# MCP23017_O8_v1_01.net
KiCad netlist of a schematic drawn in EAGLE
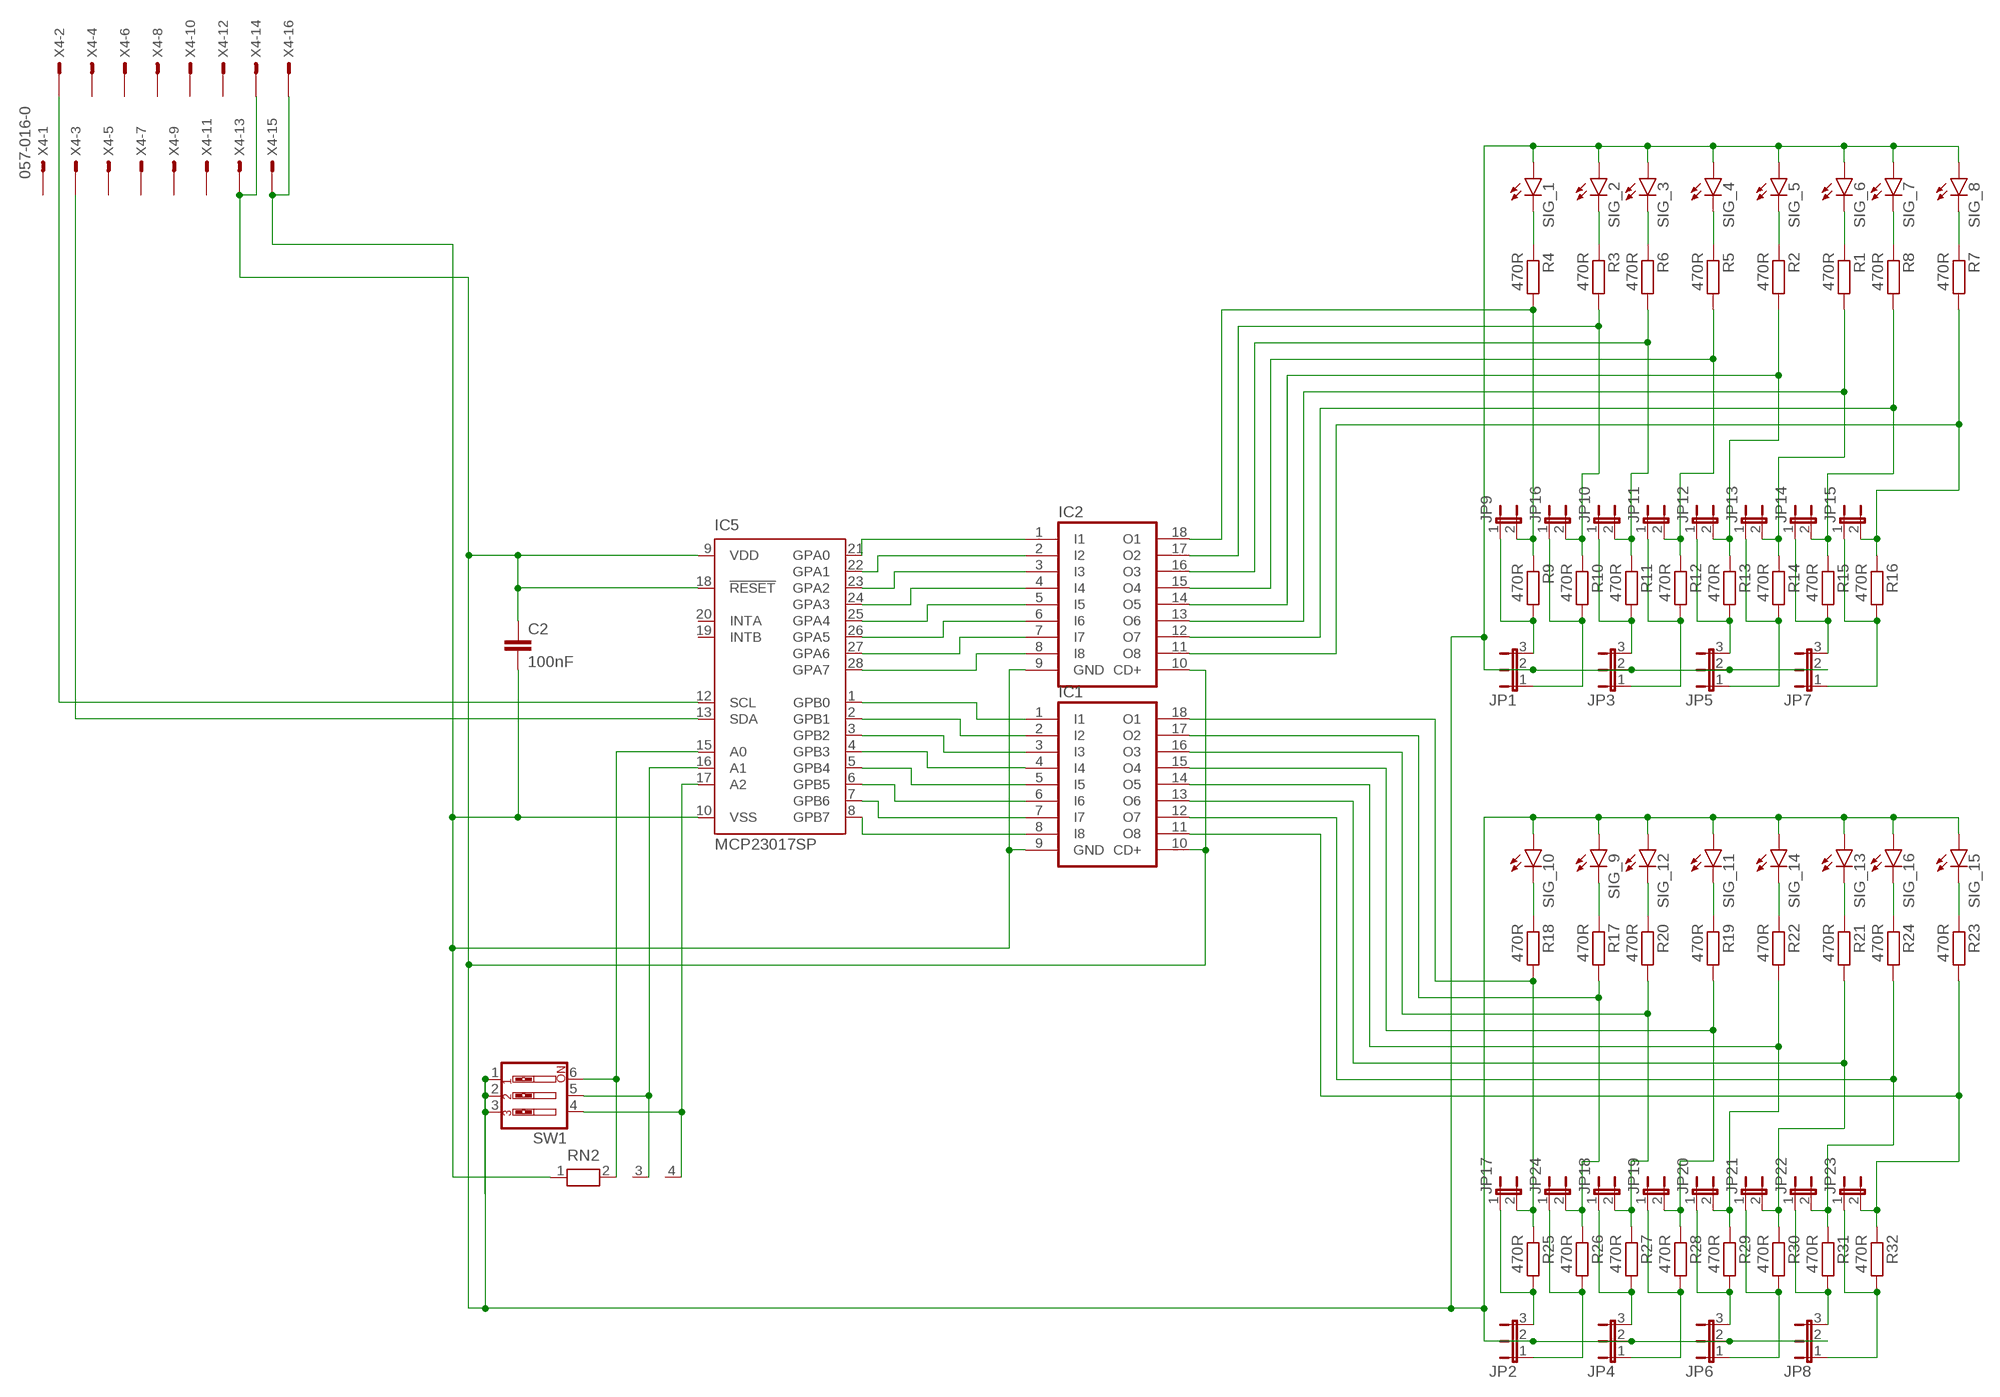
[diagram p0: schematic, sheet 1]

(export (version "E")
  (design (tool "Eeschema 10.0.6"))
  (components
    (comp (ref "C2")
      (value "100nF")
      (footprint "eagle-import:C025-024X044")
      (libsource (lib "eagle-import") (part "C-EU025-024X044"))
    )
    (comp (ref "IC1")
      (value "ULN2803A")
      (footprint "eagle-import:DIL18")
      (libsource (lib "eagle-import") (part "ULN2803A"))
    )
    (comp (ref "IC2")
      (value "ULN2803A")
      (footprint "eagle-import:DIL18")
      (libsource (lib "eagle-import") (part "ULN2803A"))
    )
    (comp (ref "IC5")
      (value "MCP23017SP")
      (footprint "eagle-import:DIL28-3")
      (libsource (lib "eagle-import") (part "MCP23017SP"))
    )
    (comp (ref "JP1")
      (value "JP2E")
      (footprint "eagle-import:JP2")
      (libsource (lib "eagle-import") (part "JP2E"))
    )
    (comp (ref "JP2")
      (value "JP2E")
      (footprint "eagle-import:JP2")
      (libsource (lib "eagle-import") (part "JP2E"))
    )
    (comp (ref "JP3")
      (value "JP2E")
      (footprint "eagle-import:JP2")
      (libsource (lib "eagle-import") (part "JP2E"))
    )
    (comp (ref "JP4")
      (value "JP2E")
      (footprint "eagle-import:JP2")
      (libsource (lib "eagle-import") (part "JP2E"))
    )
    (comp (ref "JP5")
      (value "JP2E")
      (footprint "eagle-import:JP2")
      (libsource (lib "eagle-import") (part "JP2E"))
    )
    (comp (ref "JP6")
      (value "JP2E")
      (footprint "eagle-import:JP2")
      (libsource (lib "eagle-import") (part "JP2E"))
    )
    (comp (ref "JP7")
      (value "JP2E")
      (footprint "eagle-import:JP2")
      (libsource (lib "eagle-import") (part "JP2E"))
    )
    (comp (ref "JP8")
      (value "JP2E")
      (footprint "eagle-import:JP2")
      (libsource (lib "eagle-import") (part "JP2E"))
    )
    (comp (ref "JP9")
      (value "JP1E")
      (footprint "eagle-import:JP1")
      (libsource (lib "eagle-import") (part "JP1E"))
    )
    (comp (ref "JP10")
      (value "JP1E")
      (footprint "eagle-import:JP1")
      (libsource (lib "eagle-import") (part "JP1E"))
    )
    (comp (ref "JP11")
      (value "JP1E")
      (footprint "eagle-import:JP1")
      (libsource (lib "eagle-import") (part "JP1E"))
    )
    (comp (ref "JP12")
      (value "JP1E")
      (footprint "eagle-import:JP1")
      (libsource (lib "eagle-import") (part "JP1E"))
    )
    (comp (ref "JP13")
      (value "JP1E")
      (footprint "eagle-import:JP1")
      (libsource (lib "eagle-import") (part "JP1E"))
    )
    (comp (ref "JP14")
      (value "JP1E")
      (footprint "eagle-import:JP1")
      (libsource (lib "eagle-import") (part "JP1E"))
    )
    (comp (ref "JP15")
      (value "JP1E")
      (footprint "eagle-import:JP1")
      (libsource (lib "eagle-import") (part "JP1E"))
    )
    (comp (ref "JP16")
      (value "JP1E")
      (footprint "eagle-import:JP1")
      (libsource (lib "eagle-import") (part "JP1E"))
    )
    (comp (ref "JP17")
      (value "JP1E")
      (footprint "eagle-import:JP1")
      (libsource (lib "eagle-import") (part "JP1E"))
    )
    (comp (ref "JP18")
      (value "JP1E")
      (footprint "eagle-import:JP1")
      (libsource (lib "eagle-import") (part "JP1E"))
    )
    (comp (ref "JP19")
      (value "JP1E")
      (footprint "eagle-import:JP1")
      (libsource (lib "eagle-import") (part "JP1E"))
    )
    (comp (ref "JP20")
      (value "JP1E")
      (footprint "eagle-import:JP1")
      (libsource (lib "eagle-import") (part "JP1E"))
    )
    (comp (ref "JP21")
      (value "JP1E")
      (footprint "eagle-import:JP1")
      (libsource (lib "eagle-import") (part "JP1E"))
    )
    (comp (ref "JP22")
      (value "JP1E")
      (footprint "eagle-import:JP1")
      (libsource (lib "eagle-import") (part "JP1E"))
    )
    (comp (ref "JP23")
      (value "JP1E")
      (footprint "eagle-import:JP1")
      (libsource (lib "eagle-import") (part "JP1E"))
    )
    (comp (ref "JP24")
      (value "JP1E")
      (footprint "eagle-import:JP1")
      (libsource (lib "eagle-import") (part "JP1E"))
    )
    (comp (ref "R1")
      (value "470R")
      (footprint "eagle-import:0309_10")
      (libsource (lib "eagle-import") (part "R-EU_0309/10"))
    )
    (comp (ref "R2")
      (value "470R")
      (footprint "eagle-import:0309_10")
      (libsource (lib "eagle-import") (part "R-EU_0309/10"))
    )
    (comp (ref "R3")
      (value "470R")
      (footprint "eagle-import:0309_10")
      (libsource (lib "eagle-import") (part "R-EU_0309/10"))
    )
    (comp (ref "R4")
      (value "470R")
      (footprint "eagle-import:0309_10")
      (libsource (lib "eagle-import") (part "R-EU_0309/10"))
    )
    (comp (ref "R5")
      (value "470R")
      (footprint "eagle-import:0309_10")
      (libsource (lib "eagle-import") (part "R-EU_0309/10"))
    )
    (comp (ref "R6")
      (value "470R")
      (footprint "eagle-import:0309_10")
      (libsource (lib "eagle-import") (part "R-EU_0309/10"))
    )
    (comp (ref "R7")
      (value "470R")
      (footprint "eagle-import:0309_10")
      (libsource (lib "eagle-import") (part "R-EU_0309/10"))
    )
    (comp (ref "R8")
      (value "470R")
      (footprint "eagle-import:0309_10")
      (libsource (lib "eagle-import") (part "R-EU_0309/10"))
    )
    (comp (ref "R9")
      (value "470R")
      (footprint "eagle-import:0309_10")
      (libsource (lib "eagle-import") (part "R-EU_0309/10"))
    )
    (comp (ref "R10")
      (value "470R")
      (footprint "eagle-import:0309_10")
      (libsource (lib "eagle-import") (part "R-EU_0309/10"))
    )
    (comp (ref "R11")
      (value "470R")
      (footprint "eagle-import:0309_10")
      (libsource (lib "eagle-import") (part "R-EU_0309/10"))
    )
    (comp (ref "R12")
      (value "470R")
      (footprint "eagle-import:0309_10")
      (libsource (lib "eagle-import") (part "R-EU_0309/10"))
    )
    (comp (ref "R13")
      (value "470R")
      (footprint "eagle-import:0309_10")
      (libsource (lib "eagle-import") (part "R-EU_0309/10"))
    )
    (comp (ref "R14")
      (value "470R")
      (footprint "eagle-import:0309_10")
      (libsource (lib "eagle-import") (part "R-EU_0309/10"))
    )
    (comp (ref "R15")
      (value "470R")
      (footprint "eagle-import:0309_10")
      (libsource (lib "eagle-import") (part "R-EU_0309/10"))
    )
    (comp (ref "R16")
      (value "470R")
      (footprint "eagle-import:0309_10")
      (libsource (lib "eagle-import") (part "R-EU_0309/10"))
    )
    (comp (ref "R17")
      (value "470R")
      (footprint "eagle-import:0309_10")
      (libsource (lib "eagle-import") (part "R-EU_0309/10"))
    )
    (comp (ref "R18")
      (value "470R")
      (footprint "eagle-import:0309_10")
      (libsource (lib "eagle-import") (part "R-EU_0309/10"))
    )
    (comp (ref "R19")
      (value "470R")
      (footprint "eagle-import:0309_10")
      (libsource (lib "eagle-import") (part "R-EU_0309/10"))
    )
    (comp (ref "R20")
      (value "470R")
      (footprint "eagle-import:0309_10")
      (libsource (lib "eagle-import") (part "R-EU_0309/10"))
    )
    (comp (ref "R21")
      (value "470R")
      (footprint "eagle-import:0309_10")
      (libsource (lib "eagle-import") (part "R-EU_0309/10"))
    )
    (comp (ref "R22")
      (value "470R")
      (footprint "eagle-import:0309_10")
      (libsource (lib "eagle-import") (part "R-EU_0309/10"))
    )
    (comp (ref "R23")
      (value "470R")
      (footprint "eagle-import:0309_10")
      (libsource (lib "eagle-import") (part "R-EU_0309/10"))
    )
    (comp (ref "R24")
      (value "470R")
      (footprint "eagle-import:0309_10")
      (libsource (lib "eagle-import") (part "R-EU_0309/10"))
    )
    (comp (ref "R25")
      (value "470R")
      (footprint "eagle-import:0309_10")
      (libsource (lib "eagle-import") (part "R-EU_0309/10"))
    )
    (comp (ref "R26")
      (value "470R")
      (footprint "eagle-import:0309_10")
      (libsource (lib "eagle-import") (part "R-EU_0309/10"))
    )
    (comp (ref "R27")
      (value "470R")
      (footprint "eagle-import:0309_10")
      (libsource (lib "eagle-import") (part "R-EU_0309/10"))
    )
    (comp (ref "R28")
      (value "470R")
      (footprint "eagle-import:0309_10")
      (libsource (lib "eagle-import") (part "R-EU_0309/10"))
    )
    (comp (ref "R29")
      (value "470R")
      (footprint "eagle-import:0309_10")
      (libsource (lib "eagle-import") (part "R-EU_0309/10"))
    )
    (comp (ref "R30")
      (value "470R")
      (footprint "eagle-import:0309_10")
      (libsource (lib "eagle-import") (part "R-EU_0309/10"))
    )
    (comp (ref "R31")
      (value "470R")
      (footprint "eagle-import:0309_10")
      (libsource (lib "eagle-import") (part "R-EU_0309/10"))
    )
    (comp (ref "R32")
      (value "470R")
      (footprint "eagle-import:0309_10")
      (libsource (lib "eagle-import") (part "R-EU_0309/10"))
    )
    (comp (ref "RN2")
      (value "RN03")
      (footprint "eagle-import:RN-3")
      (libsource (lib "eagle-import") (part "RN03"))
    )
    (comp (ref "SIG_1")
      (value "LED3MM")
      (footprint "eagle-import:LED3MM")
      (libsource (lib "eagle-import") (part "LED3MM"))
    )
    (comp (ref "SIG_2")
      (value "LED3MM")
      (footprint "eagle-import:LED3MM")
      (libsource (lib "eagle-import") (part "LED3MM"))
    )
    (comp (ref "SIG_3")
      (value "LED3MM")
      (footprint "eagle-import:LED3MM")
      (libsource (lib "eagle-import") (part "LED3MM"))
    )
    (comp (ref "SIG_4")
      (value "LED3MM")
      (footprint "eagle-import:LED3MM")
      (libsource (lib "eagle-import") (part "LED3MM"))
    )
    (comp (ref "SIG_5")
      (value "LED3MM")
      (footprint "eagle-import:LED3MM")
      (libsource (lib "eagle-import") (part "LED3MM"))
    )
    (comp (ref "SIG_6")
      (value "LED3MM")
      (footprint "eagle-import:LED3MM")
      (libsource (lib "eagle-import") (part "LED3MM"))
    )
    (comp (ref "SIG_7")
      (value "LED3MM")
      (footprint "eagle-import:LED3MM")
      (libsource (lib "eagle-import") (part "LED3MM"))
    )
    (comp (ref "SIG_8")
      (value "LED3MM")
      (footprint "eagle-import:LED3MM")
      (libsource (lib "eagle-import") (part "LED3MM"))
    )
    (comp (ref "SIG_9")
      (value "LED3MM")
      (footprint "eagle-import:LED3MM")
      (libsource (lib "eagle-import") (part "LED3MM"))
    )
    (comp (ref "SIG_10")
      (value "LED3MM")
      (footprint "eagle-import:LED3MM")
      (libsource (lib "eagle-import") (part "LED3MM"))
    )
    (comp (ref "SIG_11")
      (value "LED3MM")
      (footprint "eagle-import:LED3MM")
      (libsource (lib "eagle-import") (part "LED3MM"))
    )
    (comp (ref "SIG_12")
      (value "LED3MM")
      (footprint "eagle-import:LED3MM")
      (libsource (lib "eagle-import") (part "LED3MM"))
    )
    (comp (ref "SIG_13")
      (value "LED3MM")
      (footprint "eagle-import:LED3MM")
      (libsource (lib "eagle-import") (part "LED3MM"))
    )
    (comp (ref "SIG_14")
      (value "LED3MM")
      (footprint "eagle-import:LED3MM")
      (libsource (lib "eagle-import") (part "LED3MM"))
    )
    (comp (ref "SIG_15")
      (value "LED3MM")
      (footprint "eagle-import:LED3MM")
      (libsource (lib "eagle-import") (part "LED3MM"))
    )
    (comp (ref "SIG_16")
      (value "LED3MM")
      (footprint "eagle-import:LED3MM")
      (libsource (lib "eagle-import") (part "LED3MM"))
    )
    (comp (ref "SW1")
      (value "SW_DIP-3")
      (footprint "eagle-import:EDG-03")
      (libsource (lib "eagle-import") (part "SW_DIP-3"))
    )
    (comp (ref "X4")
      (value "057-016-0")
      (footprint "eagle-import:057-016-0")
      (libsource (lib "eagle-import") (part "057-016-0"))
    )
  )
  (nets
    (net (code "1") (name "Net-(IC1-CD+)") (class "Default")
      (node (ref "C2") (pin "1") (pinfunction "1_1") (pintype "passive"))
      (node (ref "IC1") (pin "10") (pinfunction "CD+_10") (pintype "passive"))
      (node (ref "IC2") (pin "10") (pinfunction "CD+_10") (pintype "passive"))
      (node (ref "IC5") (pin "18") (pinfunction "~{RESET}_18") (pintype "input"))
      (node (ref "IC5") (pin "9") (pinfunction "VDD_9") (pintype "power_in"))
      (node (ref "JP1") (pin "2") (pinfunction "2_2") (pintype "passive"))
      (node (ref "JP2") (pin "2") (pinfunction "2_2") (pintype "passive"))
      (node (ref "JP3") (pin "2") (pinfunction "2_2") (pintype "passive"))
      (node (ref "JP4") (pin "2") (pinfunction "2_2") (pintype "passive"))
      (node (ref "JP5") (pin "2") (pinfunction "2_2") (pintype "passive"))
      (node (ref "JP6") (pin "2") (pinfunction "2_2") (pintype "passive"))
      (node (ref "JP7") (pin "2") (pinfunction "2_2") (pintype "passive"))
      (node (ref "JP8") (pin "2") (pinfunction "2_2") (pintype "passive"))
      (node (ref "SIG_1") (pin "A") (pinfunction "A_A") (pintype "passive"))
      (node (ref "SIG_10") (pin "A") (pinfunction "A_A") (pintype "passive"))
      (node (ref "SIG_11") (pin "A") (pinfunction "A_A") (pintype "passive"))
      (node (ref "SIG_12") (pin "A") (pinfunction "A_A") (pintype "passive"))
      (node (ref "SIG_13") (pin "A") (pinfunction "A_A") (pintype "passive"))
      (node (ref "SIG_14") (pin "A") (pinfunction "A_A") (pintype "passive"))
      (node (ref "SIG_15") (pin "A") (pinfunction "A_A") (pintype "passive"))
      (node (ref "SIG_16") (pin "A") (pinfunction "A_A") (pintype "passive"))
      (node (ref "SIG_2") (pin "A") (pinfunction "A_A") (pintype "passive"))
      (node (ref "SIG_3") (pin "A") (pinfunction "A_A") (pintype "passive"))
      (node (ref "SIG_4") (pin "A") (pinfunction "A_A") (pintype "passive"))
      (node (ref "SIG_5") (pin "A") (pinfunction "A_A") (pintype "passive"))
      (node (ref "SIG_6") (pin "A") (pinfunction "A_A") (pintype "passive"))
      (node (ref "SIG_7") (pin "A") (pinfunction "A_A") (pintype "passive"))
      (node (ref "SIG_8") (pin "A") (pinfunction "A_A") (pintype "passive"))
      (node (ref "SIG_9") (pin "A") (pinfunction "A_A") (pintype "passive"))
      (node (ref "SW1") (pin "1") (pinfunction "1_1") (pintype "passive"))
      (node (ref "SW1") (pin "2") (pinfunction "2_2") (pintype "passive"))
      (node (ref "SW1") (pin "3") (pinfunction "3_3") (pintype "passive"))
      (node (ref "X4") (pin "13") (pinfunction "S_13") (pintype "passive"))
      (node (ref "X4") (pin "14") (pinfunction "S_14") (pintype "passive"))
    )
    (net (code "2") (name "Net-(IC1-GND)") (class "Default")
      (node (ref "C2") (pin "2") (pinfunction "2_2") (pintype "passive"))
      (node (ref "IC1") (pin "9") (pinfunction "GND_9") (pintype "power_in"))
      (node (ref "IC2") (pin "9") (pinfunction "GND_9") (pintype "power_in"))
      (node (ref "IC5") (pin "10") (pinfunction "VSS_10") (pintype "power_in"))
      (node (ref "RN2") (pin "1") (pinfunction "1_1") (pintype "passive"))
      (node (ref "X4") (pin "15") (pinfunction "S_15") (pintype "passive"))
      (node (ref "X4") (pin "16") (pinfunction "S_16") (pintype "passive"))
    )
    (net (code "3") (name "Net-(IC1-I1)") (class "Default")
      (node (ref "IC1") (pin "1") (pinfunction "I1_1") (pintype "input"))
      (node (ref "IC5") (pin "1") (pinfunction "GPB0_1") (pintype "bidirectional"))
    )
    (net (code "4") (name "Net-(IC1-I2)") (class "Default")
      (node (ref "IC1") (pin "2") (pinfunction "I2_2") (pintype "input"))
      (node (ref "IC5") (pin "2") (pinfunction "GPB1_2") (pintype "bidirectional"))
    )
    (net (code "5") (name "Net-(IC1-I3)") (class "Default")
      (node (ref "IC1") (pin "3") (pinfunction "I3_3") (pintype "input"))
      (node (ref "IC5") (pin "3") (pinfunction "GPB2_3") (pintype "bidirectional"))
    )
    (net (code "6") (name "Net-(IC1-I4)") (class "Default")
      (node (ref "IC1") (pin "4") (pinfunction "I4_4") (pintype "input"))
      (node (ref "IC5") (pin "4") (pinfunction "GPB3_4") (pintype "bidirectional"))
    )
    (net (code "7") (name "Net-(IC1-I5)") (class "Default")
      (node (ref "IC1") (pin "5") (pinfunction "I5_5") (pintype "input"))
      (node (ref "IC5") (pin "5") (pinfunction "GPB4_5") (pintype "bidirectional"))
    )
    (net (code "8") (name "Net-(IC1-I6)") (class "Default")
      (node (ref "IC1") (pin "6") (pinfunction "I6_6") (pintype "input"))
      (node (ref "IC5") (pin "6") (pinfunction "GPB5_6") (pintype "bidirectional"))
    )
    (net (code "9") (name "Net-(IC1-I7)") (class "Default")
      (node (ref "IC1") (pin "7") (pinfunction "I7_7") (pintype "input"))
      (node (ref "IC5") (pin "7") (pinfunction "GPB6_7") (pintype "bidirectional"))
    )
    (net (code "10") (name "Net-(IC1-I8)") (class "Default")
      (node (ref "IC1") (pin "8") (pinfunction "I8_8") (pintype "input"))
      (node (ref "IC5") (pin "8") (pinfunction "GPB7_8") (pintype "bidirectional"))
    )
    (net (code "11") (name "Net-(IC1-O1)") (class "Default")
      (node (ref "IC1") (pin "18") (pinfunction "O1_18") (pintype "open_collector"))
      (node (ref "JP17") (pin "2") (pinfunction "2_2") (pintype "passive"))
      (node (ref "R18") (pin "2") (pinfunction "2_2") (pintype "passive"))
      (node (ref "R25") (pin "1") (pinfunction "1_1") (pintype "passive"))
    )
    (net (code "12") (name "Net-(IC1-O2)") (class "Default")
      (node (ref "IC1") (pin "17") (pinfunction "O2_17") (pintype "open_collector"))
      (node (ref "JP24") (pin "2") (pinfunction "2_2") (pintype "passive"))
      (node (ref "R17") (pin "2") (pinfunction "2_2") (pintype "passive"))
      (node (ref "R26") (pin "1") (pinfunction "1_1") (pintype "passive"))
    )
    (net (code "13") (name "Net-(IC1-O3)") (class "Default")
      (node (ref "IC1") (pin "16") (pinfunction "O3_16") (pintype "open_collector"))
      (node (ref "JP18") (pin "2") (pinfunction "2_2") (pintype "passive"))
      (node (ref "R20") (pin "2") (pinfunction "2_2") (pintype "passive"))
      (node (ref "R27") (pin "1") (pinfunction "1_1") (pintype "passive"))
    )
    (net (code "14") (name "Net-(IC1-O4)") (class "Default")
      (node (ref "IC1") (pin "15") (pinfunction "O4_15") (pintype "open_collector"))
      (node (ref "JP19") (pin "2") (pinfunction "2_2") (pintype "passive"))
      (node (ref "R19") (pin "2") (pinfunction "2_2") (pintype "passive"))
      (node (ref "R28") (pin "1") (pinfunction "1_1") (pintype "passive"))
    )
    (net (code "15") (name "Net-(IC1-O5)") (class "Default")
      (node (ref "IC1") (pin "14") (pinfunction "O5_14") (pintype "open_collector"))
      (node (ref "JP20") (pin "2") (pinfunction "2_2") (pintype "passive"))
      (node (ref "R22") (pin "2") (pinfunction "2_2") (pintype "passive"))
      (node (ref "R29") (pin "1") (pinfunction "1_1") (pintype "passive"))
    )
    (net (code "16") (name "Net-(IC1-O6)") (class "Default")
      (node (ref "IC1") (pin "13") (pinfunction "O6_13") (pintype "open_collector"))
      (node (ref "JP21") (pin "2") (pinfunction "2_2") (pintype "passive"))
      (node (ref "R21") (pin "2") (pinfunction "2_2") (pintype "passive"))
      (node (ref "R30") (pin "1") (pinfunction "1_1") (pintype "passive"))
    )
    (net (code "17") (name "Net-(IC1-O7)") (class "Default")
      (node (ref "IC1") (pin "12") (pinfunction "O7_12") (pintype "open_collector"))
      (node (ref "JP22") (pin "2") (pinfunction "2_2") (pintype "passive"))
      (node (ref "R24") (pin "2") (pinfunction "2_2") (pintype "passive"))
      (node (ref "R31") (pin "1") (pinfunction "1_1") (pintype "passive"))
    )
    (net (code "18") (name "Net-(IC1-O8)") (class "Default")
      (node (ref "IC1") (pin "11") (pinfunction "O8_11") (pintype "open_collector"))
      (node (ref "JP23") (pin "2") (pinfunction "2_2") (pintype "passive"))
      (node (ref "R23") (pin "2") (pinfunction "2_2") (pintype "passive"))
      (node (ref "R32") (pin "1") (pinfunction "1_1") (pintype "passive"))
    )
    (net (code "19") (name "Net-(IC2-I1)") (class "Default")
      (node (ref "IC2") (pin "1") (pinfunction "I1_1") (pintype "input"))
      (node (ref "IC5") (pin "21") (pinfunction "GPA0_21") (pintype "bidirectional"))
    )
    (net (code "20") (name "Net-(IC2-I2)") (class "Default")
      (node (ref "IC2") (pin "2") (pinfunction "I2_2") (pintype "input"))
      (node (ref "IC5") (pin "22") (pinfunction "GPA1_22") (pintype "bidirectional"))
    )
    (net (code "21") (name "Net-(IC2-I3)") (class "Default")
      (node (ref "IC2") (pin "3") (pinfunction "I3_3") (pintype "input"))
      (node (ref "IC5") (pin "23") (pinfunction "GPA2_23") (pintype "bidirectional"))
    )
    (net (code "22") (name "Net-(IC2-I4)") (class "Default")
      (node (ref "IC2") (pin "4") (pinfunction "I4_4") (pintype "input"))
      (node (ref "IC5") (pin "24") (pinfunction "GPA3_24") (pintype "bidirectional"))
    )
    (net (code "23") (name "Net-(IC2-I5)") (class "Default")
      (node (ref "IC2") (pin "5") (pinfunction "I5_5") (pintype "input"))
      (node (ref "IC5") (pin "25") (pinfunction "GPA4_25") (pintype "bidirectional"))
    )
    (net (code "24") (name "Net-(IC2-I6)") (class "Default")
      (node (ref "IC2") (pin "6") (pinfunction "I6_6") (pintype "input"))
      (node (ref "IC5") (pin "26") (pinfunction "GPA5_26") (pintype "bidirectional"))
    )
    (net (code "25") (name "Net-(IC2-I7)") (class "Default")
      (node (ref "IC2") (pin "7") (pinfunction "I7_7") (pintype "input"))
      (node (ref "IC5") (pin "27") (pinfunction "GPA6_27") (pintype "bidirectional"))
    )
    (net (code "26") (name "Net-(IC2-I8)") (class "Default")
      (node (ref "IC2") (pin "8") (pinfunction "I8_8") (pintype "input"))
      (node (ref "IC5") (pin "28") (pinfunction "GPA7_28") (pintype "bidirectional"))
    )
    (net (code "27") (name "Net-(IC2-O1)") (class "Default")
      (node (ref "IC2") (pin "18") (pinfunction "O1_18") (pintype "open_collector"))
      (node (ref "JP9") (pin "2") (pinfunction "2_2") (pintype "passive"))
      (node (ref "R4") (pin "2") (pinfunction "2_2") (pintype "passive"))
      (node (ref "R9") (pin "1") (pinfunction "1_1") (pintype "passive"))
    )
    (net (code "28") (name "Net-(IC2-O2)") (class "Default")
      (node (ref "IC2") (pin "17") (pinfunction "O2_17") (pintype "open_collector"))
      (node (ref "JP16") (pin "2") (pinfunction "2_2") (pintype "passive"))
      (node (ref "R10") (pin "1") (pinfunction "1_1") (pintype "passive"))
      (node (ref "R3") (pin "2") (pinfunction "2_2") (pintype "passive"))
    )
    (net (code "29") (name "Net-(IC2-O3)") (class "Default")
      (node (ref "IC2") (pin "16") (pinfunction "O3_16") (pintype "open_collector"))
      (node (ref "JP10") (pin "2") (pinfunction "2_2") (pintype "passive"))
      (node (ref "R11") (pin "1") (pinfunction "1_1") (pintype "passive"))
      (node (ref "R6") (pin "2") (pinfunction "2_2") (pintype "passive"))
    )
    (net (code "30") (name "Net-(IC2-O4)") (class "Default")
      (node (ref "IC2") (pin "15") (pinfunction "O4_15") (pintype "open_collector"))
      (node (ref "JP11") (pin "2") (pinfunction "2_2") (pintype "passive"))
      (node (ref "R12") (pin "1") (pinfunction "1_1") (pintype "passive"))
      (node (ref "R5") (pin "2") (pinfunction "2_2") (pintype "passive"))
    )
    (net (code "31") (name "Net-(IC2-O5)") (class "Default")
      (node (ref "IC2") (pin "14") (pinfunction "O5_14") (pintype "open_collector"))
      (node (ref "JP12") (pin "2") (pinfunction "2_2") (pintype "passive"))
      (node (ref "R13") (pin "1") (pinfunction "1_1") (pintype "passive"))
      (node (ref "R2") (pin "2") (pinfunction "2_2") (pintype "passive"))
    )
    (net (code "32") (name "Net-(IC2-O6)") (class "Default")
      (node (ref "IC2") (pin "13") (pinfunction "O6_13") (pintype "open_collector"))
      (node (ref "JP13") (pin "2") (pinfunction "2_2") (pintype "passive"))
      (node (ref "R1") (pin "2") (pinfunction "2_2") (pintype "passive"))
      (node (ref "R14") (pin "1") (pinfunction "1_1") (pintype "passive"))
    )
    (net (code "33") (name "Net-(IC2-O7)") (class "Default")
      (node (ref "IC2") (pin "12") (pinfunction "O7_12") (pintype "open_collector"))
      (node (ref "JP14") (pin "2") (pinfunction "2_2") (pintype "passive"))
      (node (ref "R15") (pin "1") (pinfunction "1_1") (pintype "passive"))
      (node (ref "R8") (pin "2") (pinfunction "2_2") (pintype "passive"))
    )
    (net (code "34") (name "Net-(IC2-O8)") (class "Default")
      (node (ref "IC2") (pin "11") (pinfunction "O8_11") (pintype "open_collector"))
      (node (ref "JP15") (pin "2") (pinfunction "2_2") (pintype "passive"))
      (node (ref "R16") (pin "1") (pinfunction "1_1") (pintype "passive"))
      (node (ref "R7") (pin "2") (pinfunction "2_2") (pintype "passive"))
    )
    (net (code "35") (name "Net-(IC5-A0)") (class "Default")
      (node (ref "IC5") (pin "15") (pinfunction "A0_15") (pintype "input"))
      (node (ref "RN2") (pin "2") (pinfunction "2_2") (pintype "passive"))
      (node (ref "SW1") (pin "6") (pinfunction "6_6") (pintype "passive"))
    )
    (net (code "36") (name "Net-(IC5-A1)") (class "Default")
      (node (ref "IC5") (pin "16") (pinfunction "A1_16") (pintype "input"))
      (node (ref "RN2") (pin "3") (pinfunction "3_3") (pintype "passive"))
      (node (ref "SW1") (pin "5") (pinfunction "5_5") (pintype "passive"))
    )
    (net (code "37") (name "Net-(IC5-A2)") (class "Default")
      (node (ref "IC5") (pin "17") (pinfunction "A2_17") (pintype "input"))
      (node (ref "RN2") (pin "4") (pinfunction "4_4") (pintype "passive"))
      (node (ref "SW1") (pin "4") (pinfunction "4_4") (pintype "passive"))
    )
    (net (code "38") (name "Net-(IC5-SCL)") (class "Default")
      (node (ref "IC5") (pin "12") (pinfunction "SCL_12") (pintype "input"))
      (node (ref "X4") (pin "2") (pinfunction "S_2") (pintype "passive"))
    )
    (net (code "39") (name "Net-(IC5-SDA)") (class "Default")
      (node (ref "IC5") (pin "13") (pinfunction "SDA_13") (pintype "bidirectional"))
      (node (ref "X4") (pin "3") (pinfunction "S_3") (pintype "passive"))
    )
    (net (code "40") (name "Net-(JP1-Pad1)") (class "Default")
      (node (ref "JP1") (pin "1") (pinfunction "1_1") (pintype "passive"))
      (node (ref "JP16") (pin "1") (pinfunction "1_1") (pintype "passive"))
      (node (ref "R10") (pin "2") (pinfunction "2_2") (pintype "passive"))
    )
    (net (code "41") (name "Net-(JP1-Pad3)") (class "Default")
      (node (ref "JP1") (pin "3") (pinfunction "3_3") (pintype "passive"))
      (node (ref "JP9") (pin "1") (pinfunction "1_1") (pintype "passive"))
      (node (ref "R9") (pin "2") (pinfunction "2_2") (pintype "passive"))
    )
    (net (code "42") (name "Net-(JP2-Pad1)") (class "Default")
      (node (ref "JP2") (pin "1") (pinfunction "1_1") (pintype "passive"))
      (node (ref "JP24") (pin "1") (pinfunction "1_1") (pintype "passive"))
      (node (ref "R26") (pin "2") (pinfunction "2_2") (pintype "passive"))
    )
    (net (code "43") (name "Net-(JP10-Pad1)") (class "Default")
      (node (ref "JP10") (pin "1") (pinfunction "1_1") (pintype "passive"))
      (node (ref "JP3") (pin "3") (pinfunction "3_3") (pintype "passive"))
      (node (ref "R11") (pin "2") (pinfunction "2_2") (pintype "passive"))
    )
    (net (code "44") (name "Net-(JP11-Pad1)") (class "Default")
      (node (ref "JP11") (pin "1") (pinfunction "1_1") (pintype "passive"))
      (node (ref "JP3") (pin "1") (pinfunction "1_1") (pintype "passive"))
      (node (ref "R12") (pin "2") (pinfunction "2_2") (pintype "passive"))
    )
    (net (code "45") (name "Net-(JP12-Pad1)") (class "Default")
      (node (ref "JP12") (pin "1") (pinfunction "1_1") (pintype "passive"))
      (node (ref "JP5") (pin "3") (pinfunction "3_3") (pintype "passive"))
      (node (ref "R13") (pin "2") (pinfunction "2_2") (pintype "passive"))
    )
    (net (code "46") (name "Net-(JP13-Pad1)") (class "Default")
      (node (ref "JP13") (pin "1") (pinfunction "1_1") (pintype "passive"))
      (node (ref "JP5") (pin "1") (pinfunction "1_1") (pintype "passive"))
      (node (ref "R14") (pin "2") (pinfunction "2_2") (pintype "passive"))
    )
    (net (code "47") (name "Net-(JP14-Pad1)") (class "Default")
      (node (ref "JP14") (pin "1") (pinfunction "1_1") (pintype "passive"))
      (node (ref "JP7") (pin "3") (pinfunction "3_3") (pintype "passive"))
      (node (ref "R15") (pin "2") (pinfunction "2_2") (pintype "passive"))
    )
    (net (code "48") (name "Net-(JP15-Pad1)") (class "Default")
      (node (ref "JP15") (pin "1") (pinfunction "1_1") (pintype "passive"))
      (node (ref "JP7") (pin "1") (pinfunction "1_1") (pintype "passive"))
      (node (ref "R16") (pin "2") (pinfunction "2_2") (pintype "passive"))
    )
    (net (code "49") (name "Net-(JP17-Pad1)") (class "Default")
      (node (ref "JP17") (pin "1") (pinfunction "1_1") (pintype "passive"))
      (node (ref "JP2") (pin "3") (pinfunction "3_3") (pintype "passive"))
      (node (ref "R25") (pin "2") (pinfunction "2_2") (pintype "passive"))
    )
    (net (code "50") (name "Net-(JP18-Pad1)") (class "Default")
      (node (ref "JP18") (pin "1") (pinfunction "1_1") (pintype "passive"))
      (node (ref "JP4") (pin "3") (pinfunction "3_3") (pintype "passive"))
      (node (ref "R27") (pin "2") (pinfunction "2_2") (pintype "passive"))
    )
    (net (code "51") (name "Net-(JP19-Pad1)") (class "Default")
      (node (ref "JP19") (pin "1") (pinfunction "1_1") (pintype "passive"))
      (node (ref "JP4") (pin "1") (pinfunction "1_1") (pintype "passive"))
      (node (ref "R28") (pin "2") (pinfunction "2_2") (pintype "passive"))
    )
    (net (code "52") (name "Net-(JP20-Pad1)") (class "Default")
      (node (ref "JP20") (pin "1") (pinfunction "1_1") (pintype "passive"))
      (node (ref "JP6") (pin "3") (pinfunction "3_3") (pintype "passive"))
      (node (ref "R29") (pin "2") (pinfunction "2_2") (pintype "passive"))
    )
    (net (code "53") (name "Net-(JP21-Pad1)") (class "Default")
      (node (ref "JP21") (pin "1") (pinfunction "1_1") (pintype "passive"))
      (node (ref "JP6") (pin "1") (pinfunction "1_1") (pintype "passive"))
      (node (ref "R30") (pin "2") (pinfunction "2_2") (pintype "passive"))
    )
    (net (code "54") (name "Net-(JP22-Pad1)") (class "Default")
      (node (ref "JP22") (pin "1") (pinfunction "1_1") (pintype "passive"))
      (node (ref "JP8") (pin "3") (pinfunction "3_3") (pintype "passive"))
      (node (ref "R31") (pin "2") (pinfunction "2_2") (pintype "passive"))
    )
    (net (code "55") (name "Net-(JP23-Pad1)") (class "Default")
      (node (ref "JP23") (pin "1") (pinfunction "1_1") (pintype "passive"))
      (node (ref "JP8") (pin "1") (pinfunction "1_1") (pintype "passive"))
      (node (ref "R32") (pin "2") (pinfunction "2_2") (pintype "passive"))
    )
    (net (code "56") (name "Net-(SIG_1-C)") (class "Default")
      (node (ref "R4") (pin "1") (pinfunction "1_1") (pintype "passive"))
      (node (ref "SIG_1") (pin "K") (pinfunction "C_K") (pintype "passive"))
    )
    (net (code "57") (name "Net-(SIG_2-C)") (class "Default")
      (node (ref "R3") (pin "1") (pinfunction "1_1") (pintype "passive"))
      (node (ref "SIG_2") (pin "K") (pinfunction "C_K") (pintype "passive"))
    )
    (net (code "58") (name "Net-(SIG_3-C)") (class "Default")
      (node (ref "R6") (pin "1") (pinfunction "1_1") (pintype "passive"))
      (node (ref "SIG_3") (pin "K") (pinfunction "C_K") (pintype "passive"))
    )
    (net (code "59") (name "Net-(SIG_4-C)") (class "Default")
      (node (ref "R5") (pin "1") (pinfunction "1_1") (pintype "passive"))
      (node (ref "SIG_4") (pin "K") (pinfunction "C_K") (pintype "passive"))
    )
    (net (code "60") (name "Net-(SIG_5-C)") (class "Default")
      (node (ref "R2") (pin "1") (pinfunction "1_1") (pintype "passive"))
      (node (ref "SIG_5") (pin "K") (pinfunction "C_K") (pintype "passive"))
    )
    (net (code "61") (name "Net-(SIG_6-C)") (class "Default")
      (node (ref "R1") (pin "1") (pinfunction "1_1") (pintype "passive"))
      (node (ref "SIG_6") (pin "K") (pinfunction "C_K") (pintype "passive"))
    )
    (net (code "62") (name "Net-(SIG_7-C)") (class "Default")
      (node (ref "R8") (pin "1") (pinfunction "1_1") (pintype "passive"))
      (node (ref "SIG_7") (pin "K") (pinfunction "C_K") (pintype "passive"))
    )
    (net (code "63") (name "Net-(SIG_8-C)") (class "Default")
      (node (ref "R7") (pin "1") (pinfunction "1_1") (pintype "passive"))
      (node (ref "SIG_8") (pin "K") (pinfunction "C_K") (pintype "passive"))
    )
    (net (code "64") (name "Net-(SIG_9-C)") (class "Default")
      (node (ref "R17") (pin "1") (pinfunction "1_1") (pintype "passive"))
      (node (ref "SIG_9") (pin "K") (pinfunction "C_K") (pintype "passive"))
    )
    (net (code "65") (name "Net-(SIG_10-C)") (class "Default")
      (node (ref "R18") (pin "1") (pinfunction "1_1") (pintype "passive"))
      (node (ref "SIG_10") (pin "K") (pinfunction "C_K") (pintype "passive"))
    )
    (net (code "66") (name "Net-(SIG_11-C)") (class "Default")
      (node (ref "R19") (pin "1") (pinfunction "1_1") (pintype "passive"))
      (node (ref "SIG_11") (pin "K") (pinfunction "C_K") (pintype "passive"))
    )
    (net (code "67") (name "Net-(SIG_12-C)") (class "Default")
      (node (ref "R20") (pin "1") (pinfunction "1_1") (pintype "passive"))
      (node (ref "SIG_12") (pin "K") (pinfunction "C_K") (pintype "passive"))
    )
    (net (code "68") (name "Net-(SIG_13-C)") (class "Default")
      (node (ref "R21") (pin "1") (pinfunction "1_1") (pintype "passive"))
      (node (ref "SIG_13") (pin "K") (pinfunction "C_K") (pintype "passive"))
    )
    (net (code "69") (name "Net-(SIG_14-C)") (class "Default")
      (node (ref "R22") (pin "1") (pinfunction "1_1") (pintype "passive"))
      (node (ref "SIG_14") (pin "K") (pinfunction "C_K") (pintype "passive"))
    )
    (net (code "70") (name "Net-(SIG_15-C)") (class "Default")
      (node (ref "R23") (pin "1") (pinfunction "1_1") (pintype "passive"))
      (node (ref "SIG_15") (pin "K") (pinfunction "C_K") (pintype "passive"))
    )
    (net (code "71") (name "Net-(SIG_16-C)") (class "Default")
      (node (ref "R24") (pin "1") (pinfunction "1_1") (pintype "passive"))
      (node (ref "SIG_16") (pin "K") (pinfunction "C_K") (pintype "passive"))
    )
    (net (code "72") (name "unconnected-(IC5-INTA-Pad20)") (class "Default")
      (node (ref "IC5") (pin "20") (pinfunction "INTA_20") (pintype "output"))
    )
    (net (code "73") (name "unconnected-(IC5-INTB-Pad19)") (class "Default")
      (node (ref "IC5") (pin "19") (pinfunction "INTB_19") (pintype "output"))
    )
    (net (code "74") (name "unconnected-(X4A-S-Pad1)") (class "Default")
      (node (ref "X4") (pin "1") (pinfunction "S_1") (pintype "passive"))
    )
    (net (code "75") (name "unconnected-(X4B-S-Pad10)") (class "Default")
      (node (ref "X4") (pin "10") (pinfunction "S_10") (pintype "passive"))
    )
    (net (code "76") (name "unconnected-(X4C-S-Pad11)") (class "Default")
      (node (ref "X4") (pin "11") (pinfunction "S_11") (pintype "passive"))
    )
    (net (code "77") (name "unconnected-(X4D-S-Pad12)") (class "Default")
      (node (ref "X4") (pin "12") (pinfunction "S_12") (pintype "passive"))
    )
    (net (code "78") (name "unconnected-(X4K-S-Pad4)") (class "Default")
      (node (ref "X4") (pin "4") (pinfunction "S_4") (pintype "passive"))
    )
    (net (code "79") (name "unconnected-(X4L-S-Pad5)") (class "Default")
      (node (ref "X4") (pin "5") (pinfunction "S_5") (pintype "passive"))
    )
    (net (code "80") (name "unconnected-(X4M-S-Pad6)") (class "Default")
      (node (ref "X4") (pin "6") (pinfunction "S_6") (pintype "passive"))
    )
    (net (code "81") (name "unconnected-(X4N-S-Pad7)") (class "Default")
      (node (ref "X4") (pin "7") (pinfunction "S_7") (pintype "passive"))
    )
    (net (code "82") (name "unconnected-(X4O-S-Pad8)") (class "Default")
      (node (ref "X4") (pin "8") (pinfunction "S_8") (pintype "passive"))
    )
    (net (code "83") (name "unconnected-(X4P-S-Pad9)") (class "Default")
      (node (ref "X4") (pin "9") (pinfunction "S_9") (pintype "passive"))
    )
  )
)
